# PCB_L298_Board.net
KiCad netlist of a schematic drawn in Altium Designer
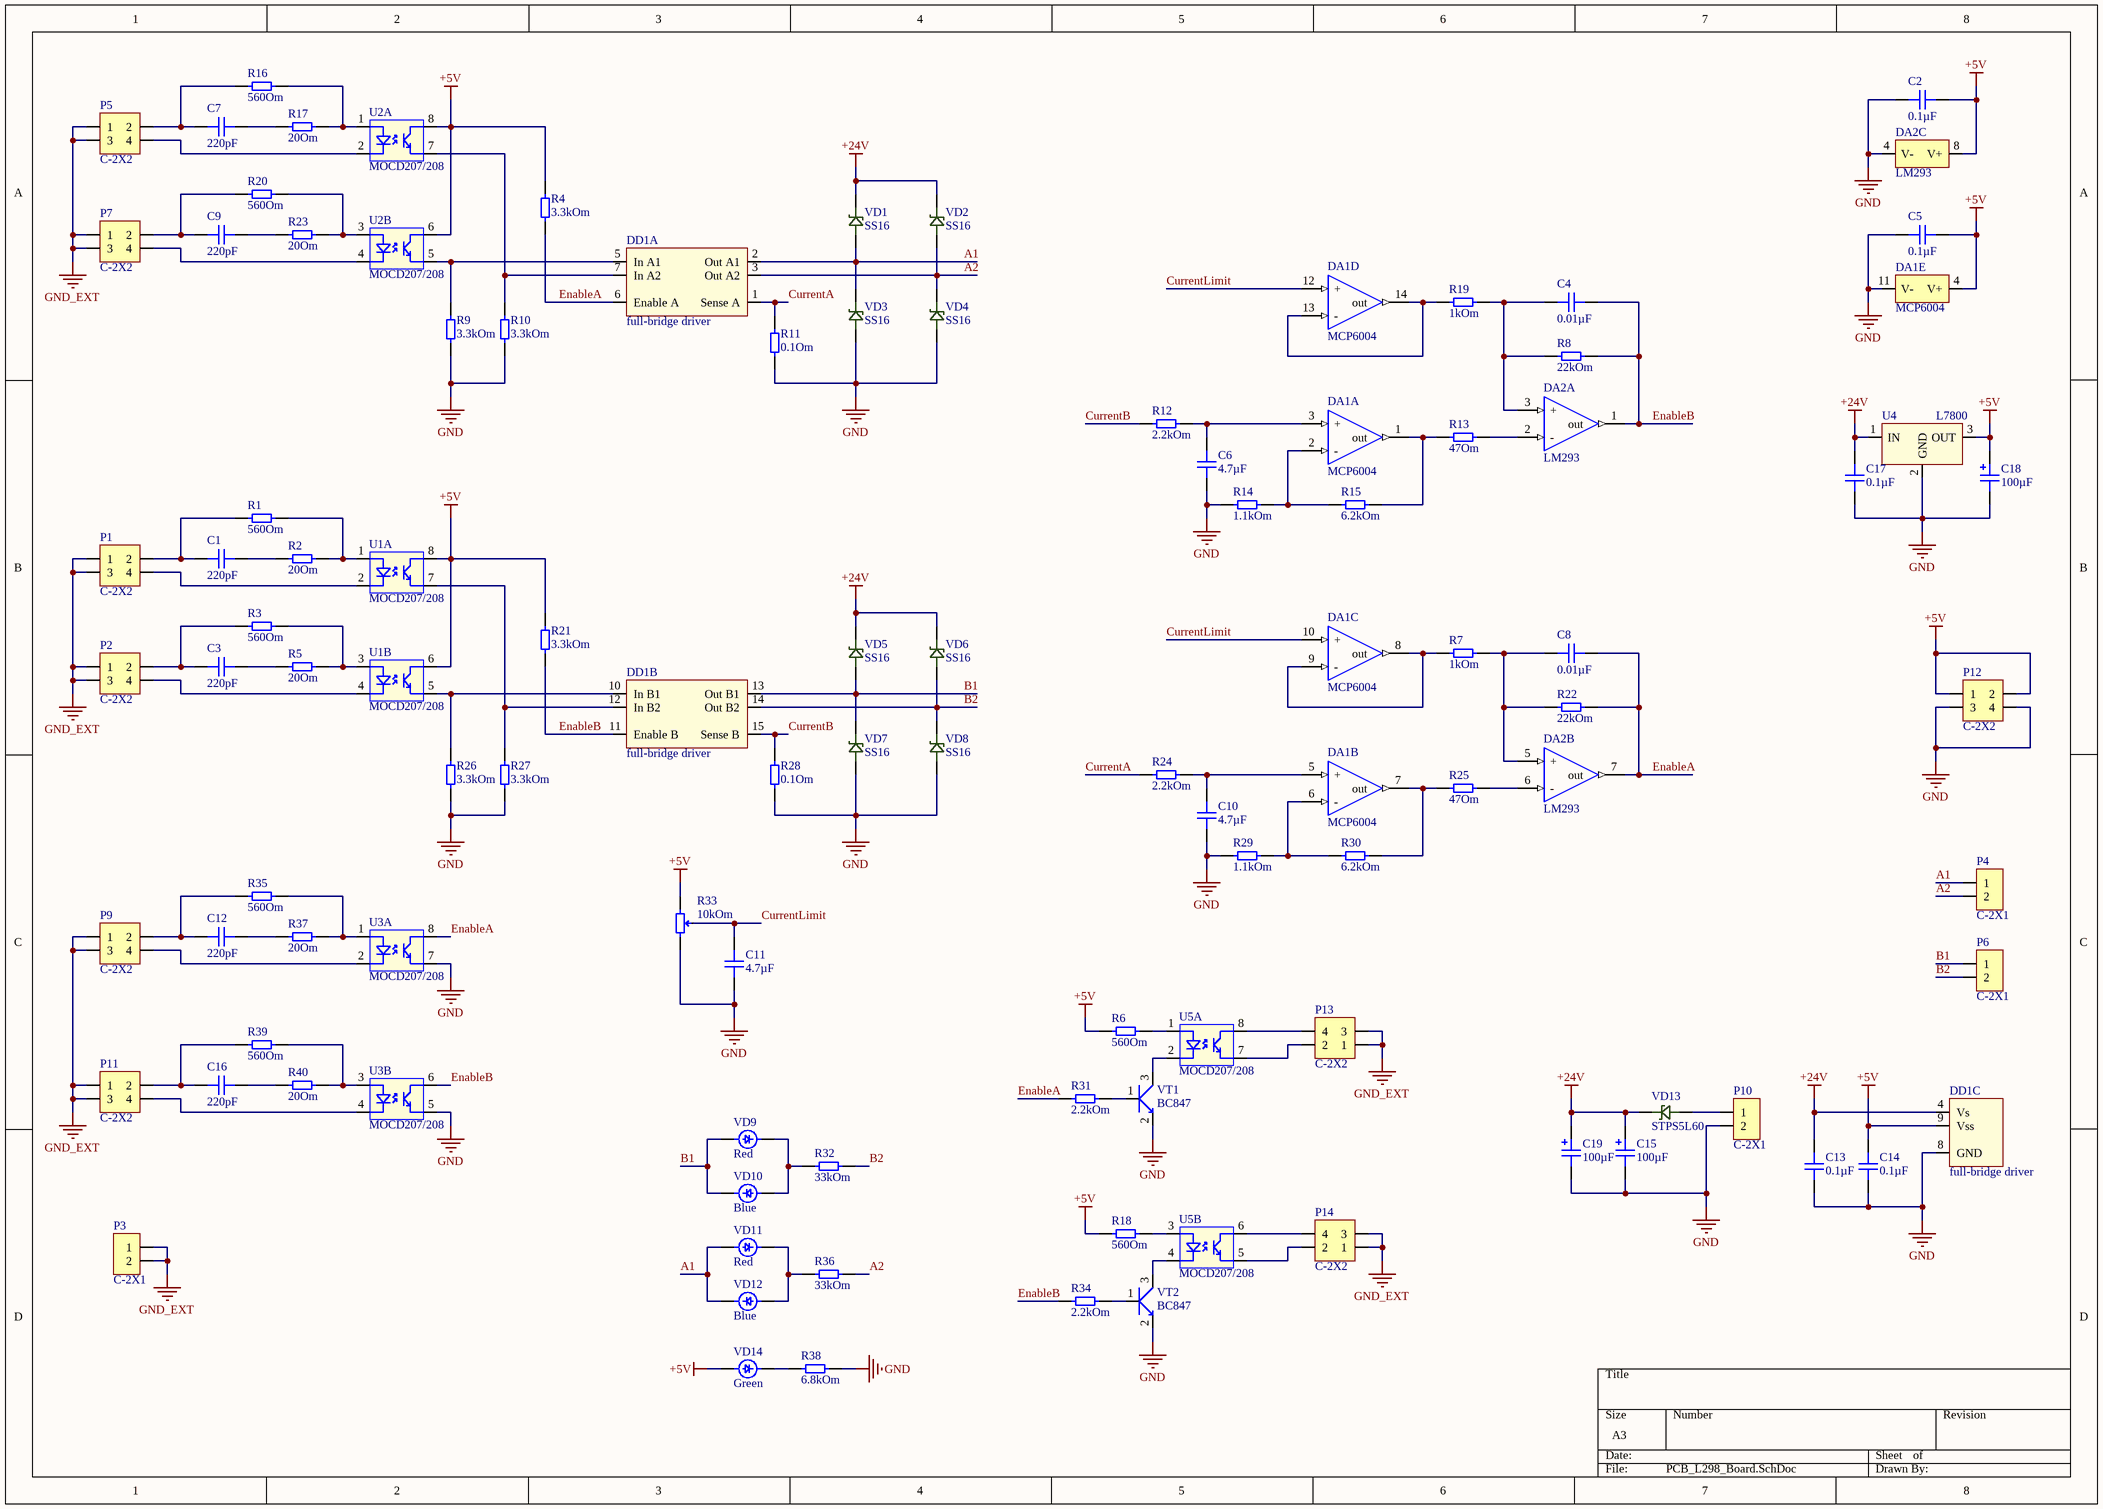
[diagram p0: PCB_L298_Board.SchDoc]

(export (version "E")
  (design (tool "Eeschema 10.0.6"))
  (components
    (comp (ref "C1")
      (value "Ceramic")
      (footprint "SMD-1206")
      (fields (field (name "CAPACITY") "220pF"))
      (libsource (lib "xCapacitors") (part "Ceramic"))
    )
    (comp (ref "C2")
      (value "Ceramic")
      (footprint "SMD-1206")
      (fields (field (name "CAPACITY") "0.1µF"))
      (libsource (lib "xCapacitors") (part "Ceramic"))
    )
    (comp (ref "C3")
      (value "Ceramic")
      (footprint "SMD-1206")
      (fields (field (name "CAPACITY") "220pF"))
      (libsource (lib "xCapacitors") (part "Ceramic"))
    )
    (comp (ref "C4")
      (value "Ceramic")
      (footprint "SMD-1206")
      (fields (field (name "CAPACITY") "0.01µF"))
      (libsource (lib "xCapacitors") (part "Ceramic"))
    )
    (comp (ref "C5")
      (value "Ceramic")
      (footprint "SMD-1206")
      (fields (field (name "CAPACITY") "0.1µF"))
      (libsource (lib "xCapacitors") (part "Ceramic"))
    )
    (comp (ref "C6")
      (value "Ceramic")
      (footprint "SMD-1206")
      (fields (field (name "CAPACITY") "4.7µF"))
      (libsource (lib "xCapacitors") (part "Ceramic"))
    )
    (comp (ref "C7")
      (value "Ceramic")
      (footprint "SMD-1206")
      (fields (field (name "CAPACITY") "220pF"))
      (libsource (lib "xCapacitors") (part "Ceramic"))
    )
    (comp (ref "C8")
      (value "Ceramic")
      (footprint "SMD-1206")
      (fields (field (name "CAPACITY") "0.01µF"))
      (libsource (lib "xCapacitors") (part "Ceramic"))
    )
    (comp (ref "C9")
      (value "Ceramic")
      (footprint "SMD-1206")
      (fields (field (name "CAPACITY") "220pF"))
      (libsource (lib "xCapacitors") (part "Ceramic"))
    )
    (comp (ref "C10")
      (value "Ceramic")
      (footprint "SMD-1206")
      (fields (field (name "CAPACITY") "4.7µF"))
      (libsource (lib "xCapacitors") (part "Ceramic"))
    )
    (comp (ref "C11")
      (value "Ceramic")
      (footprint "SMD-1206")
      (fields (field (name "CAPACITY") "4.7µF"))
      (libsource (lib "xCapacitors") (part "Ceramic"))
    )
    (comp (ref "C12")
      (value "Ceramic")
      (footprint "SMD-1206")
      (fields (field (name "CAPACITY") "220pF"))
      (libsource (lib "xCapacitors") (part "Ceramic"))
    )
    (comp (ref "C13")
      (value "Ceramic")
      (footprint "SMD-1206")
      (fields (field (name "CAPACITY") "0.1µF"))
      (libsource (lib "xCapacitors") (part "Ceramic"))
    )
    (comp (ref "C14")
      (value "Ceramic")
      (footprint "SMD-1206")
      (fields (field (name "CAPACITY") "0.1µF"))
      (libsource (lib "xCapacitors") (part "Ceramic"))
    )
    (comp (ref "C15")
      (value "Polar")
      (footprint "BAR-(8-11)(3.175)")
      (fields (field (name "CAPACITY") "100µF"))
      (libsource (lib "xCapacitors") (part "Polar"))
    )
    (comp (ref "C16")
      (value "Ceramic")
      (footprint "SMD-1206")
      (fields (field (name "CAPACITY") "220pF"))
      (libsource (lib "xCapacitors") (part "Ceramic"))
    )
    (comp (ref "C17")
      (value "Ceramic")
      (footprint "SMD-1206")
      (fields (field (name "CAPACITY") "0.1µF"))
      (libsource (lib "xCapacitors") (part "Ceramic"))
    )
    (comp (ref "C18")
      (value "Polar")
      (footprint "BAR-(6.3-11)(2.54)")
      (fields (field (name "CAPACITY") "100µF"))
      (libsource (lib "xCapacitors") (part "Polar"))
    )
    (comp (ref "C19")
      (value "Polar")
      (footprint "BAR-(8-11)(3.175)")
      (fields (field (name "CAPACITY") "100µF"))
      (libsource (lib "xCapacitors") (part "Polar"))
    )
    (comp (ref "DA1")
      (value "MCP6004")
      (footprint "SOP-14")
      (description "1 MHz, Low-Power Op Amp")
      (libsource (lib "xAmplifiers") (part "MCP6004"))
    )
    (comp (ref "DA2")
      (value "LM293")
      (footprint "SOP-8")
      (description "Low Power Dual Voltage Comparators")
      (libsource (lib "xAmplifiers") (part "LM293"))
    )
    (comp (ref "DD1")
      (value "full-bridge driver")
      (footprint "MULTIWATT-15")
      (libsource (lib "xMotorDrivers") (part "L298"))
    )
    (comp (ref "P1") (value "C-2X2") (footprint "C-2X2(2.54)") (libsource (lib "xConnectors") (part "C-2X2")))
    (comp (ref "P2") (value "C-2X2") (footprint "C-2X2(2.54)") (libsource (lib "xConnectors") (part "C-2X2")))
    (comp (ref "P3") (value "C-2X1") (footprint "C-2X1(2.54)") (libsource (lib "") (part "C-2X1_1")))
    (comp (ref "P4")
      (value "C-2X1")
      (footprint "CB2-10-11-X(5.08)")
      (libsource (lib "xConnectors") (part "C-2X1"))
    )
    (comp (ref "P5") (value "C-2X2") (footprint "C-2X2(2.54)") (libsource (lib "xConnectors") (part "C-2X2")))
    (comp (ref "P6")
      (value "C-2X1")
      (footprint "CB2-10-11-X(5.08)")
      (libsource (lib "xConnectors") (part "C-2X1"))
    )
    (comp (ref "P7") (value "C-2X2") (footprint "C-2X2(2.54)") (libsource (lib "xConnectors") (part "C-2X2")))
    (comp (ref "P9") (value "C-2X2") (footprint "C-2X2(2.54)") (libsource (lib "xConnectors") (part "C-2X2")))
    (comp (ref "P10")
      (value "C-2X1")
      (footprint "CB2-10-11-X(5.08)")
      (libsource (lib "xConnectors") (part "C-2X1"))
    )
    (comp (ref "P11")
      (value "C-2X2")
      (footprint "C-2X2(2.54)")
      (libsource (lib "xConnectors") (part "C-2X2"))
    )
    (comp (ref "P12")
      (value "C-2X2")
      (footprint "C-2X2(2.54)")
      (libsource (lib "xConnectors") (part "C-2X2"))
    )
    (comp (ref "P13") (value "C-2X2") (footprint "C-2X2(2.54)") (libsource (lib "") (part "C-2X2_1")))
    (comp (ref "P14") (value "C-2X2") (footprint "C-2X2(2.54)") (libsource (lib "") (part "C-2X2_1")))
    (comp (ref "R1")
      (value "560Om")
      (footprint "SMD-1206")
      (fields (field (name "Comment") "Resistor"))
      (libsource (lib "xResistors") (part "Resistor"))
    )
    (comp (ref "R2")
      (value "20Om")
      (footprint "SMD-1206")
      (fields (field (name "Comment") "Resistor"))
      (libsource (lib "xResistors") (part "Resistor"))
    )
    (comp (ref "R3")
      (value "560Om")
      (footprint "SMD-1206")
      (fields (field (name "Comment") "Resistor"))
      (libsource (lib "xResistors") (part "Resistor"))
    )
    (comp (ref "R4")
      (value "3.3kOm")
      (footprint "SMD-1206")
      (fields (field (name "Comment") "Resistor"))
      (libsource (lib "xResistors") (part "Resistor"))
    )
    (comp (ref "R5")
      (value "20Om")
      (footprint "SMD-1206")
      (fields (field (name "Comment") "Resistor"))
      (libsource (lib "xResistors") (part "Resistor"))
    )
    (comp (ref "R6")
      (value "560Om")
      (footprint "SMD-1206")
      (fields (field (name "Comment") "Resistor"))
      (libsource (lib "xResistors") (part "Resistor"))
    )
    (comp (ref "R7")
      (value "1kOm")
      (footprint "SMD-1206")
      (fields (field (name "Comment") "Resistor"))
      (libsource (lib "xResistors") (part "Resistor"))
    )
    (comp (ref "R8")
      (value "22kOm")
      (footprint "SMD-1206")
      (fields (field (name "Comment") "Resistor"))
      (libsource (lib "xResistors") (part "Resistor"))
    )
    (comp (ref "R9")
      (value "3.3kOm")
      (footprint "SMD-1206")
      (fields (field (name "Comment") "Resistor"))
      (libsource (lib "xResistors") (part "Resistor"))
    )
    (comp (ref "R10")
      (value "3.3kOm")
      (footprint "SMD-1206")
      (fields (field (name "Comment") "Resistor"))
      (libsource (lib "xResistors") (part "Resistor"))
    )
    (comp (ref "R11")
      (value "0.1Om")
      (footprint "SMD-2512")
      (fields (field (name "Comment") "Resistor"))
      (libsource (lib "xResistors") (part "Resistor"))
    )
    (comp (ref "R12")
      (value "2.2kOm")
      (footprint "SMD-1206")
      (fields (field (name "Comment") "Resistor"))
      (libsource (lib "xResistors") (part "Resistor"))
    )
    (comp (ref "R13")
      (value "47Om")
      (footprint "SMD-1206")
      (fields (field (name "Comment") "Resistor"))
      (libsource (lib "xResistors") (part "Resistor"))
    )
    (comp (ref "R14")
      (value "1.1kOm")
      (footprint "SMD-1206")
      (fields (field (name "Comment") "Resistor"))
      (libsource (lib "xResistors") (part "Resistor"))
    )
    (comp (ref "R15")
      (value "6.2kOm")
      (footprint "SMD-1206")
      (fields (field (name "Comment") "Resistor"))
      (libsource (lib "xResistors") (part "Resistor"))
    )
    (comp (ref "R16")
      (value "560Om")
      (footprint "SMD-1206")
      (fields (field (name "Comment") "Resistor"))
      (libsource (lib "xResistors") (part "Resistor"))
    )
    (comp (ref "R17")
      (value "20Om")
      (footprint "SMD-1206")
      (fields (field (name "Comment") "Resistor"))
      (libsource (lib "xResistors") (part "Resistor"))
    )
    (comp (ref "R18")
      (value "560Om")
      (footprint "SMD-1206")
      (fields (field (name "Comment") "Resistor"))
      (libsource (lib "xResistors") (part "Resistor"))
    )
    (comp (ref "R19")
      (value "1kOm")
      (footprint "SMD-1206")
      (fields (field (name "Comment") "Resistor"))
      (libsource (lib "xResistors") (part "Resistor"))
    )
    (comp (ref "R20")
      (value "560Om")
      (footprint "SMD-1206")
      (fields (field (name "Comment") "Resistor"))
      (libsource (lib "xResistors") (part "Resistor"))
    )
    (comp (ref "R21")
      (value "3.3kOm")
      (footprint "SMD-1206")
      (fields (field (name "Comment") "Resistor"))
      (libsource (lib "xResistors") (part "Resistor"))
    )
    (comp (ref "R22")
      (value "22kOm")
      (footprint "SMD-1206")
      (fields (field (name "Comment") "Resistor"))
      (libsource (lib "xResistors") (part "Resistor"))
    )
    (comp (ref "R23")
      (value "20Om")
      (footprint "SMD-1206")
      (fields (field (name "Comment") "Resistor"))
      (libsource (lib "xResistors") (part "Resistor"))
    )
    (comp (ref "R24")
      (value "2.2kOm")
      (footprint "SMD-1206")
      (fields (field (name "Comment") "Resistor"))
      (libsource (lib "xResistors") (part "Resistor"))
    )
    (comp (ref "R25")
      (value "47Om")
      (footprint "SMD-1206")
      (fields (field (name "Comment") "Resistor"))
      (libsource (lib "xResistors") (part "Resistor"))
    )
    (comp (ref "R26")
      (value "3.3kOm")
      (footprint "SMD-1206")
      (fields (field (name "Comment") "Resistor"))
      (libsource (lib "xResistors") (part "Resistor"))
    )
    (comp (ref "R27")
      (value "3.3kOm")
      (footprint "SMD-1206")
      (fields (field (name "Comment") "Resistor"))
      (libsource (lib "xResistors") (part "Resistor"))
    )
    (comp (ref "R28")
      (value "0.1Om")
      (footprint "SMD-2512")
      (fields (field (name "Comment") "Resistor"))
      (libsource (lib "xResistors") (part "Resistor"))
    )
    (comp (ref "R29")
      (value "1.1kOm")
      (footprint "SMD-1206")
      (fields (field (name "Comment") "Resistor"))
      (libsource (lib "xResistors") (part "Resistor"))
    )
    (comp (ref "R30")
      (value "6.2kOm")
      (footprint "SMD-1206")
      (fields (field (name "Comment") "Resistor"))
      (libsource (lib "xResistors") (part "Resistor"))
    )
    (comp (ref "R31")
      (value "2.2kOm")
      (footprint "SMD-1206")
      (fields (field (name "Comment") "Resistor"))
      (libsource (lib "xResistors") (part "Resistor"))
    )
    (comp (ref "R32")
      (value "33kOm")
      (footprint "SMD-1206")
      (fields (field (name "Comment") "Resistor"))
      (libsource (lib "xResistors") (part "Resistor"))
    )
    (comp (ref "R33")
      (value "Tuning")
      (footprint "3296(bot only)")
      (fields (field (name "RESISTANCE") "10kOm"))
      (libsource (lib "xResistors") (part "Tuning"))
    )
    (comp (ref "R34")
      (value "2.2kOm")
      (footprint "SMD-1206")
      (fields (field (name "Comment") "Resistor"))
      (libsource (lib "xResistors") (part "Resistor"))
    )
    (comp (ref "R35")
      (value "560Om")
      (footprint "SMD-1206")
      (fields (field (name "Comment") "Resistor"))
      (libsource (lib "xResistors") (part "Resistor"))
    )
    (comp (ref "R36")
      (value "33kOm")
      (footprint "SMD-1206")
      (fields (field (name "Comment") "Resistor"))
      (libsource (lib "xResistors") (part "Resistor"))
    )
    (comp (ref "R37")
      (value "20Om")
      (footprint "SMD-1206")
      (fields (field (name "Comment") "Resistor"))
      (libsource (lib "xResistors") (part "Resistor"))
    )
    (comp (ref "R38")
      (value "6.8kOm")
      (footprint "SMD-1206")
      (fields (field (name "Comment") "Resistor"))
      (libsource (lib "xResistors") (part "Resistor"))
    )
    (comp (ref "R39")
      (value "560Om")
      (footprint "SMD-1206")
      (fields (field (name "Comment") "Resistor"))
      (libsource (lib "xResistors") (part "Resistor"))
    )
    (comp (ref "R40")
      (value "20Om")
      (footprint "SMD-1206")
      (fields (field (name "Comment") "Resistor"))
      (libsource (lib "xResistors") (part "Resistor"))
    )
    (comp (ref "U1")
      (value "MOCD207/208")
      (footprint "SOP-8")
      (description "Dual-channel Phototransistor Small Outline Surface\r\nMount Optocouplers")
      (libsource (lib "xOpticals") (part "MOCD207/208"))
    )
    (comp (ref "U2")
      (value "MOCD207/208")
      (footprint "SOP-8")
      (description "Dual-channel Phototransistor Small Outline Surface\r\nMount Optocouplers")
      (libsource (lib "xOpticals") (part "MOCD207/208"))
    )
    (comp (ref "U3")
      (value "MOCD207/208")
      (footprint "SOP-8")
      (description "Dual-channel Phototransistor Small Outline Surface\r\nMount Optocouplers")
      (libsource (lib "xOpticals") (part "MOCD207/208"))
    )
    (comp (ref "U4")
      (value "L7800")
      (footprint "TO-220(EX-1)")
      (description "L7800 series of three-terminal positive regulators")
      (libsource (lib "xVoltageRegulators") (part "L7800"))
    )
    (comp (ref "U5")
      (value "MOCD207/208")
      (footprint "SOP-8")
      (description "Dual-channel Phototransistor Small Outline Surface\r\nMount Optocouplers")
      (libsource (lib "xOpticals") (part "MOCD207/208"))
    )
    (comp (ref "VD1") (value "SS16") (footprint "SMB(DO-214AA)") (libsource (lib "xDiodes") (part "SS16")))
    (comp (ref "VD2") (value "SS16") (footprint "SMB(DO-214AA)") (libsource (lib "xDiodes") (part "SS16")))
    (comp (ref "VD3") (value "SS16") (footprint "SMB(DO-214AA)") (libsource (lib "xDiodes") (part "SS16")))
    (comp (ref "VD4") (value "SS16") (footprint "SMB(DO-214AA)") (libsource (lib "xDiodes") (part "SS16")))
    (comp (ref "VD5") (value "SS16") (footprint "SMB(DO-214AA)") (libsource (lib "xDiodes") (part "SS16")))
    (comp (ref "VD6") (value "SS16") (footprint "SMB(DO-214AA)") (libsource (lib "xDiodes") (part "SS16")))
    (comp (ref "VD7") (value "SS16") (footprint "SMB(DO-214AA)") (libsource (lib "xDiodes") (part "SS16")))
    (comp (ref "VD8") (value "SS16") (footprint "SMB(DO-214AA)") (libsource (lib "xDiodes") (part "SS16")))
    (comp (ref "VD9")
      (value "Red")
      (footprint "SMD-1206")
      (description "universal template")
      (libsource (lib "xDiodes") (part "Led"))
    )
    (comp (ref "VD10")
      (value "Blue")
      (footprint "SMD-1206")
      (description "universal template")
      (libsource (lib "xDiodes") (part "Led"))
    )
    (comp (ref "VD11")
      (value "Red")
      (footprint "SMD-1206")
      (description "universal template")
      (libsource (lib "xDiodes") (part "Led"))
    )
    (comp (ref "VD12")
      (value "Blue")
      (footprint "SMD-1206")
      (description "universal template")
      (libsource (lib "xDiodes") (part "Led"))
    )
    (comp (ref "VD13")
      (value "STPS5L60")
      (footprint "SMC(DO-214AB)")
      (description "5 A - 60 V power Schottky rectifier")
      (libsource (lib "xDiodes") (part "STPS5L60"))
    )
    (comp (ref "VD14")
      (value "Green")
      (footprint "SMD-1206")
      (description "universal template")
      (libsource (lib "xDiodes") (part "Led"))
    )
    (comp (ref "VT1")
      (value "BC847")
      (footprint "SOT-23")
      (description "NPN Plastic-Encapsulate Transistors")
      (libsource (lib "xSemiconductors") (part "BC847"))
    )
    (comp (ref "VT2")
      (value "BC847")
      (footprint "SOT-23")
      (description "NPN Plastic-Encapsulate Transistors")
      (libsource (lib "xSemiconductors") (part "BC847"))
    )
  )
  (nets
    (net (code "1") (name "+5V") (class "Default")
      (node (ref "C14") (pin "1") (pinfunction "1_1") (pintype "passive"))
      (node (ref "C18") (pin "2") (pinfunction "2_2") (pintype "passive"))
      (node (ref "C2") (pin "2") (pinfunction "2_2") (pintype "passive"))
      (node (ref "C5") (pin "1") (pinfunction "1_1") (pintype "passive"))
      (node (ref "DA1") (pin "4") (pinfunction "V+_4") (pintype "power_in"))
      (node (ref "DA2") (pin "8") (pinfunction "V+_8") (pintype "power_in"))
      (node (ref "DD1") (pin "9") (pinfunction "Vss_9") (pintype "passive"))
      (node (ref "P12") (pin "1") (pinfunction "1_1") (pintype "passive"))
      (node (ref "P12") (pin "2") (pinfunction "2_2") (pintype "passive"))
      (node (ref "R18") (pin "2") (pinfunction "2_2") (pintype "passive"))
      (node (ref "R21") (pin "2") (pinfunction "2_2") (pintype "passive"))
      (node (ref "R33") (pin "1") (pinfunction "1_1") (pintype "passive"))
      (node (ref "R4") (pin "2") (pinfunction "2_2") (pintype "passive"))
      (node (ref "R6") (pin "2") (pinfunction "2_2") (pintype "passive"))
      (node (ref "U1") (pin "6") (pinfunction "6_6") (pintype "passive"))
      (node (ref "U1") (pin "8") (pinfunction "8_8") (pintype "passive"))
      (node (ref "U2") (pin "6") (pinfunction "6_6") (pintype "passive"))
      (node (ref "U2") (pin "8") (pinfunction "8_8") (pintype "passive"))
      (node (ref "U4") (pin "3") (pinfunction "OUT_3") (pintype "passive"))
      (node (ref "VD14") (pin "1") (pinfunction "1_1") (pintype "passive"))
    )
    (net (code "2") (name "+24V") (class "Default")
      (node (ref "C13") (pin "1") (pinfunction "1_1") (pintype "passive"))
      (node (ref "C15") (pin "2") (pinfunction "2_2") (pintype "passive"))
      (node (ref "C17") (pin "1") (pinfunction "1_1") (pintype "passive"))
      (node (ref "C19") (pin "2") (pinfunction "2_2") (pintype "passive"))
      (node (ref "DD1") (pin "4") (pinfunction "Vs_4") (pintype "passive"))
      (node (ref "U4") (pin "1") (pinfunction "IN_1") (pintype "passive"))
      (node (ref "VD1") (pin "2") (pinfunction "2_2") (pintype "passive"))
      (node (ref "VD13") (pin "2") (pinfunction "2_2") (pintype "passive"))
      (node (ref "VD2") (pin "2") (pinfunction "2_2") (pintype "passive"))
      (node (ref "VD5") (pin "2") (pinfunction "2_2") (pintype "passive"))
      (node (ref "VD6") (pin "2") (pinfunction "2_2") (pintype "passive"))
    )
    (net (code "3") (name "/A1") (class "Default")
      (node (ref "DD1") (pin "2") (pinfunction "Out_A1_2") (pintype "passive"))
      (node (ref "P4") (pin "1") (pinfunction "1_1") (pintype "passive"))
      (node (ref "VD1") (pin "1") (pinfunction "1_1") (pintype "passive"))
      (node (ref "VD11") (pin "1") (pinfunction "1_1") (pintype "passive"))
      (node (ref "VD12") (pin "2") (pinfunction "2_2") (pintype "passive"))
      (node (ref "VD3") (pin "2") (pinfunction "2_2") (pintype "passive"))
    )
    (net (code "4") (name "/A2") (class "Default")
      (node (ref "DD1") (pin "3") (pinfunction "Out_A2_3") (pintype "passive"))
      (node (ref "P4") (pin "2") (pinfunction "2_2") (pintype "passive"))
      (node (ref "R36") (pin "1") (pinfunction "1_1") (pintype "passive"))
      (node (ref "VD2") (pin "1") (pinfunction "1_1") (pintype "passive"))
      (node (ref "VD4") (pin "2") (pinfunction "2_2") (pintype "passive"))
    )
    (net (code "5") (name "/B1") (class "Default")
      (node (ref "DD1") (pin "13") (pinfunction "Out_B1_13") (pintype "passive"))
      (node (ref "P6") (pin "1") (pinfunction "1_1") (pintype "passive"))
      (node (ref "VD10") (pin "2") (pinfunction "2_2") (pintype "passive"))
      (node (ref "VD5") (pin "1") (pinfunction "1_1") (pintype "passive"))
      (node (ref "VD7") (pin "2") (pinfunction "2_2") (pintype "passive"))
      (node (ref "VD9") (pin "1") (pinfunction "1_1") (pintype "passive"))
    )
    (net (code "6") (name "/B2") (class "Default")
      (node (ref "DD1") (pin "14") (pinfunction "Out_B2_14") (pintype "passive"))
      (node (ref "P6") (pin "2") (pinfunction "2_2") (pintype "passive"))
      (node (ref "R32") (pin "1") (pinfunction "1_1") (pintype "passive"))
      (node (ref "VD6") (pin "1") (pinfunction "1_1") (pintype "passive"))
      (node (ref "VD8") (pin "2") (pinfunction "2_2") (pintype "passive"))
    )
    (net (code "7") (name "/CurrentA") (class "Default")
      (node (ref "DD1") (pin "1") (pinfunction "Sense_A_1") (pintype "passive"))
      (node (ref "R11") (pin "2") (pinfunction "2_2") (pintype "passive"))
      (node (ref "R24") (pin "2") (pinfunction "2_2") (pintype "passive"))
    )
    (net (code "8") (name "/CurrentB") (class "Default")
      (node (ref "DD1") (pin "15") (pinfunction "Sense_B_15") (pintype "passive"))
      (node (ref "R12") (pin "2") (pinfunction "2_2") (pintype "passive"))
      (node (ref "R28") (pin "2") (pinfunction "2_2") (pintype "passive"))
    )
    (net (code "9") (name "/CurrentLimit") (class "Default")
      (node (ref "C11") (pin "1") (pinfunction "1_1") (pintype "passive"))
      (node (ref "DA1") (pin "10") (pinfunction "+_10") (pintype "input"))
      (node (ref "DA1") (pin "12") (pinfunction "+_12") (pintype "input"))
      (node (ref "R33") (pin "2") (pinfunction "2_2") (pintype "passive"))
    )
    (net (code "10") (name "/EnableA") (class "Default")
      (node (ref "C8") (pin "2") (pinfunction "2_2") (pintype "passive"))
      (node (ref "DA2") (pin "7") (pinfunction "out_7") (pintype "output"))
      (node (ref "DD1") (pin "6") (pinfunction "Enable_A_6") (pintype "passive"))
      (node (ref "R22") (pin "2") (pinfunction "2_2") (pintype "passive"))
      (node (ref "R31") (pin "2") (pinfunction "2_2") (pintype "passive"))
      (node (ref "R4") (pin "1") (pinfunction "1_1") (pintype "passive"))
      (node (ref "U3") (pin "8") (pinfunction "8_8") (pintype "passive"))
    )
    (net (code "11") (name "/EnableB") (class "Default")
      (node (ref "C4") (pin "2") (pinfunction "2_2") (pintype "passive"))
      (node (ref "DA2") (pin "1") (pinfunction "out_1") (pintype "output"))
      (node (ref "DD1") (pin "11") (pinfunction "Enable_B_11") (pintype "passive"))
      (node (ref "R21") (pin "1") (pinfunction "1_1") (pintype "passive"))
      (node (ref "R34") (pin "2") (pinfunction "2_2") (pintype "passive"))
      (node (ref "R8") (pin "2") (pinfunction "2_2") (pintype "passive"))
      (node (ref "U3") (pin "6") (pinfunction "6_6") (pintype "passive"))
    )
    (net (code "12") (name "GND") (class "Default")
      (node (ref "C10") (pin "2") (pinfunction "2_2") (pintype "passive"))
      (node (ref "C11") (pin "2") (pinfunction "2_2") (pintype "passive"))
      (node (ref "C13") (pin "2") (pinfunction "2_2") (pintype "passive"))
      (node (ref "C14") (pin "2") (pinfunction "2_2") (pintype "passive"))
      (node (ref "C15") (pin "1") (pinfunction "1_1") (pintype "passive"))
      (node (ref "C17") (pin "2") (pinfunction "2_2") (pintype "passive"))
      (node (ref "C18") (pin "1") (pinfunction "1_1") (pintype "passive"))
      (node (ref "C19") (pin "1") (pinfunction "1_1") (pintype "passive"))
      (node (ref "C2") (pin "1") (pinfunction "1_1") (pintype "passive"))
      (node (ref "C5") (pin "2") (pinfunction "2_2") (pintype "passive"))
      (node (ref "C6") (pin "2") (pinfunction "2_2") (pintype "passive"))
      (node (ref "DA1") (pin "11") (pinfunction "V-_11") (pintype "power_in"))
      (node (ref "DA2") (pin "4") (pinfunction "V-_4") (pintype "power_in"))
      (node (ref "DD1") (pin "8") (pinfunction "GND_8") (pintype "passive"))
      (node (ref "P10") (pin "2") (pinfunction "2_2") (pintype "passive"))
      (node (ref "P12") (pin "3") (pinfunction "3_3") (pintype "passive"))
      (node (ref "P12") (pin "4") (pinfunction "4_4") (pintype "passive"))
      (node (ref "R10") (pin "1") (pinfunction "1_1") (pintype "passive"))
      (node (ref "R11") (pin "1") (pinfunction "1_1") (pintype "passive"))
      (node (ref "R14") (pin "2") (pinfunction "2_2") (pintype "passive"))
      (node (ref "R26") (pin "1") (pinfunction "1_1") (pintype "passive"))
      (node (ref "R27") (pin "1") (pinfunction "1_1") (pintype "passive"))
      (node (ref "R28") (pin "1") (pinfunction "1_1") (pintype "passive"))
      (node (ref "R29") (pin "2") (pinfunction "2_2") (pintype "passive"))
      (node (ref "R33") (pin "3") (pinfunction "3_3") (pintype "passive"))
      (node (ref "R38") (pin "1") (pinfunction "1_1") (pintype "passive"))
      (node (ref "R9") (pin "1") (pinfunction "1_1") (pintype "passive"))
      (node (ref "U3") (pin "5") (pinfunction "5_5") (pintype "passive"))
      (node (ref "U3") (pin "7") (pinfunction "7_7") (pintype "passive"))
      (node (ref "U4") (pin "2") (pinfunction "GND_2") (pintype "passive"))
      (node (ref "VD3") (pin "1") (pinfunction "1_1") (pintype "passive"))
      (node (ref "VD4") (pin "1") (pinfunction "1_1") (pintype "passive"))
      (node (ref "VD7") (pin "1") (pinfunction "1_1") (pintype "passive"))
      (node (ref "VD8") (pin "1") (pinfunction "1_1") (pintype "passive"))
      (node (ref "VT1") (pin "2") (pinfunction "E_2") (pintype "passive"))
      (node (ref "VT2") (pin "2") (pinfunction "E_2") (pintype "passive"))
    )
    (net (code "13") (name "GND_EXT") (class "Default")
      (node (ref "P1") (pin "1") (pinfunction "1_1") (pintype "passive"))
      (node (ref "P1") (pin "3") (pinfunction "3_3") (pintype "passive"))
      (node (ref "P11") (pin "1") (pinfunction "1_1") (pintype "passive"))
      (node (ref "P11") (pin "3") (pinfunction "3_3") (pintype "passive"))
      (node (ref "P13") (pin "1") (pinfunction "1_1") (pintype "passive"))
      (node (ref "P13") (pin "3") (pinfunction "3_3") (pintype "passive"))
      (node (ref "P14") (pin "1") (pinfunction "1_1") (pintype "passive"))
      (node (ref "P14") (pin "3") (pinfunction "3_3") (pintype "passive"))
      (node (ref "P2") (pin "1") (pinfunction "1_1") (pintype "passive"))
      (node (ref "P2") (pin "3") (pinfunction "3_3") (pintype "passive"))
      (node (ref "P3") (pin "1") (pinfunction "1_1") (pintype "passive"))
      (node (ref "P3") (pin "2") (pinfunction "2_2") (pintype "passive"))
      (node (ref "P5") (pin "1") (pinfunction "1_1") (pintype "passive"))
      (node (ref "P5") (pin "3") (pinfunction "3_3") (pintype "passive"))
      (node (ref "P7") (pin "1") (pinfunction "1_1") (pintype "passive"))
      (node (ref "P7") (pin "3") (pinfunction "3_3") (pintype "passive"))
      (node (ref "P9") (pin "1") (pinfunction "1_1") (pintype "passive"))
      (node (ref "P9") (pin "3") (pinfunction "3_3") (pintype "passive"))
    )
    (net (code "14") (name "Net-(C1-Pad1)") (class "Default")
      (node (ref "C1") (pin "1") (pinfunction "1_1") (pintype "passive"))
      (node (ref "P1") (pin "2") (pinfunction "2_2") (pintype "passive"))
      (node (ref "R1") (pin "2") (pinfunction "2_2") (pintype "passive"))
    )
    (net (code "15") (name "Net-(C1-Pad2)") (class "Default")
      (node (ref "C1") (pin "2") (pinfunction "2_2") (pintype "passive"))
      (node (ref "R2") (pin "2") (pinfunction "2_2") (pintype "passive"))
    )
    (net (code "16") (name "Net-(C3-Pad1)") (class "Default")
      (node (ref "C3") (pin "1") (pinfunction "1_1") (pintype "passive"))
      (node (ref "P2") (pin "2") (pinfunction "2_2") (pintype "passive"))
      (node (ref "R3") (pin "2") (pinfunction "2_2") (pintype "passive"))
    )
    (net (code "17") (name "Net-(C3-Pad2)") (class "Default")
      (node (ref "C3") (pin "2") (pinfunction "2_2") (pintype "passive"))
      (node (ref "R5") (pin "2") (pinfunction "2_2") (pintype "passive"))
    )
    (net (code "18") (name "Net-(C7-Pad1)") (class "Default")
      (node (ref "C7") (pin "1") (pinfunction "1_1") (pintype "passive"))
      (node (ref "P5") (pin "2") (pinfunction "2_2") (pintype "passive"))
      (node (ref "R16") (pin "2") (pinfunction "2_2") (pintype "passive"))
    )
    (net (code "19") (name "Net-(C7-Pad2)") (class "Default")
      (node (ref "C7") (pin "2") (pinfunction "2_2") (pintype "passive"))
      (node (ref "R17") (pin "2") (pinfunction "2_2") (pintype "passive"))
    )
    (net (code "20") (name "Net-(C9-Pad1)") (class "Default")
      (node (ref "C9") (pin "1") (pinfunction "1_1") (pintype "passive"))
      (node (ref "P7") (pin "2") (pinfunction "2_2") (pintype "passive"))
      (node (ref "R20") (pin "2") (pinfunction "2_2") (pintype "passive"))
    )
    (net (code "21") (name "Net-(C9-Pad2)") (class "Default")
      (node (ref "C9") (pin "2") (pinfunction "2_2") (pintype "passive"))
      (node (ref "R23") (pin "2") (pinfunction "2_2") (pintype "passive"))
    )
    (net (code "22") (name "Net-(C12-Pad1)") (class "Default")
      (node (ref "C12") (pin "1") (pinfunction "1_1") (pintype "passive"))
      (node (ref "P9") (pin "2") (pinfunction "2_2") (pintype "passive"))
      (node (ref "R35") (pin "2") (pinfunction "2_2") (pintype "passive"))
    )
    (net (code "23") (name "Net-(C12-Pad2)") (class "Default")
      (node (ref "C12") (pin "2") (pinfunction "2_2") (pintype "passive"))
      (node (ref "R37") (pin "2") (pinfunction "2_2") (pintype "passive"))
    )
    (net (code "24") (name "Net-(C16-Pad1)") (class "Default")
      (node (ref "C16") (pin "1") (pinfunction "1_1") (pintype "passive"))
      (node (ref "P11") (pin "2") (pinfunction "2_2") (pintype "passive"))
      (node (ref "R39") (pin "2") (pinfunction "2_2") (pintype "passive"))
    )
    (net (code "25") (name "Net-(C16-Pad2)") (class "Default")
      (node (ref "C16") (pin "2") (pinfunction "2_2") (pintype "passive"))
      (node (ref "R40") (pin "2") (pinfunction "2_2") (pintype "passive"))
    )
    (net (code "26") (name "Net-(DA1A-+)") (class "Default")
      (node (ref "C6") (pin "1") (pinfunction "1_1") (pintype "passive"))
      (node (ref "DA1") (pin "3") (pinfunction "+_3") (pintype "input"))
      (node (ref "R12") (pin "1") (pinfunction "1_1") (pintype "passive"))
    )
    (net (code "27") (name "Net-(DA1A--)") (class "Default")
      (node (ref "DA1") (pin "2") (pinfunction "-_2") (pintype "input"))
      (node (ref "R14") (pin "1") (pinfunction "1_1") (pintype "passive"))
      (node (ref "R15") (pin "2") (pinfunction "2_2") (pintype "passive"))
    )
    (net (code "28") (name "Net-(DA1A-out)") (class "Default")
      (node (ref "DA1") (pin "1") (pinfunction "out_1") (pintype "output"))
      (node (ref "R13") (pin "2") (pinfunction "2_2") (pintype "passive"))
      (node (ref "R15") (pin "1") (pinfunction "1_1") (pintype "passive"))
    )
    (net (code "29") (name "Net-(DA1B-+)") (class "Default")
      (node (ref "C10") (pin "1") (pinfunction "1_1") (pintype "passive"))
      (node (ref "DA1") (pin "5") (pinfunction "+_5") (pintype "input"))
      (node (ref "R24") (pin "1") (pinfunction "1_1") (pintype "passive"))
    )
    (net (code "30") (name "Net-(DA1B--)") (class "Default")
      (node (ref "DA1") (pin "6") (pinfunction "-_6") (pintype "input"))
      (node (ref "R29") (pin "1") (pinfunction "1_1") (pintype "passive"))
      (node (ref "R30") (pin "2") (pinfunction "2_2") (pintype "passive"))
    )
    (net (code "31") (name "Net-(DA1B-out)") (class "Default")
      (node (ref "DA1") (pin "7") (pinfunction "out_7") (pintype "output"))
      (node (ref "R25") (pin "2") (pinfunction "2_2") (pintype "passive"))
      (node (ref "R30") (pin "1") (pinfunction "1_1") (pintype "passive"))
    )
    (net (code "32") (name "Net-(DA1C--)") (class "Default")
      (node (ref "DA1") (pin "8") (pinfunction "out_8") (pintype "output"))
      (node (ref "DA1") (pin "9") (pinfunction "-_9") (pintype "input"))
      (node (ref "R7") (pin "2") (pinfunction "2_2") (pintype "passive"))
    )
    (net (code "33") (name "Net-(DA1D--)") (class "Default")
      (node (ref "DA1") (pin "13") (pinfunction "-_13") (pintype "input"))
      (node (ref "DA1") (pin "14") (pinfunction "out_14") (pintype "output"))
      (node (ref "R19") (pin "2") (pinfunction "2_2") (pintype "passive"))
    )
    (net (code "34") (name "Net-(DA2A-+)") (class "Default")
      (node (ref "C4") (pin "1") (pinfunction "1_1") (pintype "passive"))
      (node (ref "DA2") (pin "3") (pinfunction "+_3") (pintype "input"))
      (node (ref "R19") (pin "1") (pinfunction "1_1") (pintype "passive"))
      (node (ref "R8") (pin "1") (pinfunction "1_1") (pintype "passive"))
    )
    (net (code "35") (name "Net-(DA2A--)") (class "Default")
      (node (ref "DA2") (pin "2") (pinfunction "-_2") (pintype "input"))
      (node (ref "R13") (pin "1") (pinfunction "1_1") (pintype "passive"))
    )
    (net (code "36") (name "Net-(DA2B-+)") (class "Default")
      (node (ref "C8") (pin "1") (pinfunction "1_1") (pintype "passive"))
      (node (ref "DA2") (pin "5") (pinfunction "+_5") (pintype "input"))
      (node (ref "R22") (pin "1") (pinfunction "1_1") (pintype "passive"))
      (node (ref "R7") (pin "1") (pinfunction "1_1") (pintype "passive"))
    )
    (net (code "37") (name "Net-(DA2B--)") (class "Default")
      (node (ref "DA2") (pin "6") (pinfunction "-_6") (pintype "input"))
      (node (ref "R25") (pin "1") (pinfunction "1_1") (pintype "passive"))
    )
    (net (code "38") (name "Net-(DD1A-In_A1)") (class "Default")
      (node (ref "DD1") (pin "5") (pinfunction "In_A1_5") (pintype "passive"))
      (node (ref "R9") (pin "2") (pinfunction "2_2") (pintype "passive"))
      (node (ref "U2") (pin "5") (pinfunction "5_5") (pintype "passive"))
    )
    (net (code "39") (name "Net-(DD1A-In_A2)") (class "Default")
      (node (ref "DD1") (pin "7") (pinfunction "In_A2_7") (pintype "passive"))
      (node (ref "R10") (pin "2") (pinfunction "2_2") (pintype "passive"))
      (node (ref "U2") (pin "7") (pinfunction "7_7") (pintype "passive"))
    )
    (net (code "40") (name "Net-(DD1B-In_B1)") (class "Default")
      (node (ref "DD1") (pin "10") (pinfunction "In_B1_10") (pintype "passive"))
      (node (ref "R26") (pin "2") (pinfunction "2_2") (pintype "passive"))
      (node (ref "U1") (pin "5") (pinfunction "5_5") (pintype "passive"))
    )
    (net (code "41") (name "Net-(DD1B-In_B2)") (class "Default")
      (node (ref "DD1") (pin "12") (pinfunction "In_B2_12") (pintype "passive"))
      (node (ref "R27") (pin "2") (pinfunction "2_2") (pintype "passive"))
      (node (ref "U1") (pin "7") (pinfunction "7_7") (pintype "passive"))
    )
    (net (code "42") (name "Net-(P1-Pad4)") (class "Default")
      (node (ref "P1") (pin "4") (pinfunction "4_4") (pintype "passive"))
      (node (ref "U1") (pin "2") (pinfunction "2_2") (pintype "passive"))
    )
    (net (code "43") (name "Net-(P2-Pad4)") (class "Default")
      (node (ref "P2") (pin "4") (pinfunction "4_4") (pintype "passive"))
      (node (ref "U1") (pin "4") (pinfunction "4_4") (pintype "passive"))
    )
    (net (code "44") (name "Net-(P5-Pad4)") (class "Default")
      (node (ref "P5") (pin "4") (pinfunction "4_4") (pintype "passive"))
      (node (ref "U2") (pin "2") (pinfunction "2_2") (pintype "passive"))
    )
    (net (code "45") (name "Net-(P7-Pad4)") (class "Default")
      (node (ref "P7") (pin "4") (pinfunction "4_4") (pintype "passive"))
      (node (ref "U2") (pin "4") (pinfunction "4_4") (pintype "passive"))
    )
    (net (code "46") (name "Net-(P9-Pad4)") (class "Default")
      (node (ref "P9") (pin "4") (pinfunction "4_4") (pintype "passive"))
      (node (ref "U3") (pin "2") (pinfunction "2_2") (pintype "passive"))
    )
    (net (code "47") (name "Net-(P10-Pad1)") (class "Default")
      (node (ref "P10") (pin "1") (pinfunction "1_1") (pintype "passive"))
      (node (ref "VD13") (pin "1") (pinfunction "1_1") (pintype "passive"))
    )
    (net (code "48") (name "Net-(P11-Pad4)") (class "Default")
      (node (ref "P11") (pin "4") (pinfunction "4_4") (pintype "passive"))
      (node (ref "U3") (pin "4") (pinfunction "4_4") (pintype "passive"))
    )
    (net (code "49") (name "Net-(P13-Pad2)") (class "Default")
      (node (ref "P13") (pin "2") (pinfunction "2_2") (pintype "passive"))
      (node (ref "U5") (pin "7") (pinfunction "7_7") (pintype "passive"))
    )
    (net (code "50") (name "Net-(P13-Pad4)") (class "Default")
      (node (ref "P13") (pin "4") (pinfunction "4_4") (pintype "passive"))
      (node (ref "U5") (pin "8") (pinfunction "8_8") (pintype "passive"))
    )
    (net (code "51") (name "Net-(P14-Pad2)") (class "Default")
      (node (ref "P14") (pin "2") (pinfunction "2_2") (pintype "passive"))
      (node (ref "U5") (pin "5") (pinfunction "5_5") (pintype "passive"))
    )
    (net (code "52") (name "Net-(P14-Pad4)") (class "Default")
      (node (ref "P14") (pin "4") (pinfunction "4_4") (pintype "passive"))
      (node (ref "U5") (pin "6") (pinfunction "6_6") (pintype "passive"))
    )
    (net (code "53") (name "Net-(R1-Pad1)") (class "Default")
      (node (ref "R1") (pin "1") (pinfunction "1_1") (pintype "passive"))
      (node (ref "R2") (pin "1") (pinfunction "1_1") (pintype "passive"))
      (node (ref "U1") (pin "1") (pinfunction "1_1") (pintype "passive"))
    )
    (net (code "54") (name "Net-(R3-Pad1)") (class "Default")
      (node (ref "R3") (pin "1") (pinfunction "1_1") (pintype "passive"))
      (node (ref "R5") (pin "1") (pinfunction "1_1") (pintype "passive"))
      (node (ref "U1") (pin "3") (pinfunction "3_3") (pintype "passive"))
    )
    (net (code "55") (name "Net-(R6-Pad1)") (class "Default")
      (node (ref "R6") (pin "1") (pinfunction "1_1") (pintype "passive"))
      (node (ref "U5") (pin "1") (pinfunction "1_1") (pintype "passive"))
    )
    (net (code "56") (name "Net-(R16-Pad1)") (class "Default")
      (node (ref "R16") (pin "1") (pinfunction "1_1") (pintype "passive"))
      (node (ref "R17") (pin "1") (pinfunction "1_1") (pintype "passive"))
      (node (ref "U2") (pin "1") (pinfunction "1_1") (pintype "passive"))
    )
    (net (code "57") (name "Net-(R18-Pad1)") (class "Default")
      (node (ref "R18") (pin "1") (pinfunction "1_1") (pintype "passive"))
      (node (ref "U5") (pin "3") (pinfunction "3_3") (pintype "passive"))
    )
    (net (code "58") (name "Net-(R20-Pad1)") (class "Default")
      (node (ref "R20") (pin "1") (pinfunction "1_1") (pintype "passive"))
      (node (ref "R23") (pin "1") (pinfunction "1_1") (pintype "passive"))
      (node (ref "U2") (pin "3") (pinfunction "3_3") (pintype "passive"))
    )
    (net (code "59") (name "Net-(R32-Pad2)") (class "Default")
      (node (ref "R32") (pin "2") (pinfunction "2_2") (pintype "passive"))
      (node (ref "VD10") (pin "1") (pinfunction "1_1") (pintype "passive"))
      (node (ref "VD9") (pin "2") (pinfunction "2_2") (pintype "passive"))
    )
    (net (code "60") (name "Net-(R35-Pad1)") (class "Default")
      (node (ref "R35") (pin "1") (pinfunction "1_1") (pintype "passive"))
      (node (ref "R37") (pin "1") (pinfunction "1_1") (pintype "passive"))
      (node (ref "U3") (pin "1") (pinfunction "1_1") (pintype "passive"))
    )
    (net (code "61") (name "Net-(R36-Pad2)") (class "Default")
      (node (ref "R36") (pin "2") (pinfunction "2_2") (pintype "passive"))
      (node (ref "VD11") (pin "2") (pinfunction "2_2") (pintype "passive"))
      (node (ref "VD12") (pin "1") (pinfunction "1_1") (pintype "passive"))
    )
    (net (code "62") (name "Net-(R38-Pad2)") (class "Default")
      (node (ref "R38") (pin "2") (pinfunction "2_2") (pintype "passive"))
      (node (ref "VD14") (pin "2") (pinfunction "2_2") (pintype "passive"))
    )
    (net (code "63") (name "Net-(R39-Pad1)") (class "Default")
      (node (ref "R39") (pin "1") (pinfunction "1_1") (pintype "passive"))
      (node (ref "R40") (pin "1") (pinfunction "1_1") (pintype "passive"))
      (node (ref "U3") (pin "3") (pinfunction "3_3") (pintype "passive"))
    )
    (net (code "64") (name "Net-(VT1-B)") (class "Default")
      (node (ref "R31") (pin "1") (pinfunction "1_1") (pintype "passive"))
      (node (ref "VT1") (pin "1") (pinfunction "B_1") (pintype "passive"))
    )
    (net (code "65") (name "Net-(VT1-C)") (class "Default")
      (node (ref "U5") (pin "2") (pinfunction "2_2") (pintype "passive"))
      (node (ref "VT1") (pin "3") (pinfunction "C_3") (pintype "passive"))
    )
    (net (code "66") (name "Net-(VT2-B)") (class "Default")
      (node (ref "R34") (pin "1") (pinfunction "1_1") (pintype "passive"))
      (node (ref "VT2") (pin "1") (pinfunction "B_1") (pintype "passive"))
    )
    (net (code "67") (name "Net-(VT2-C)") (class "Default")
      (node (ref "U5") (pin "4") (pinfunction "4_4") (pintype "passive"))
      (node (ref "VT2") (pin "3") (pinfunction "C_3") (pintype "passive"))
    )
  )
)
